# ir_transceiver.net
KiCad netlist of a schematic drawn in EAGLE
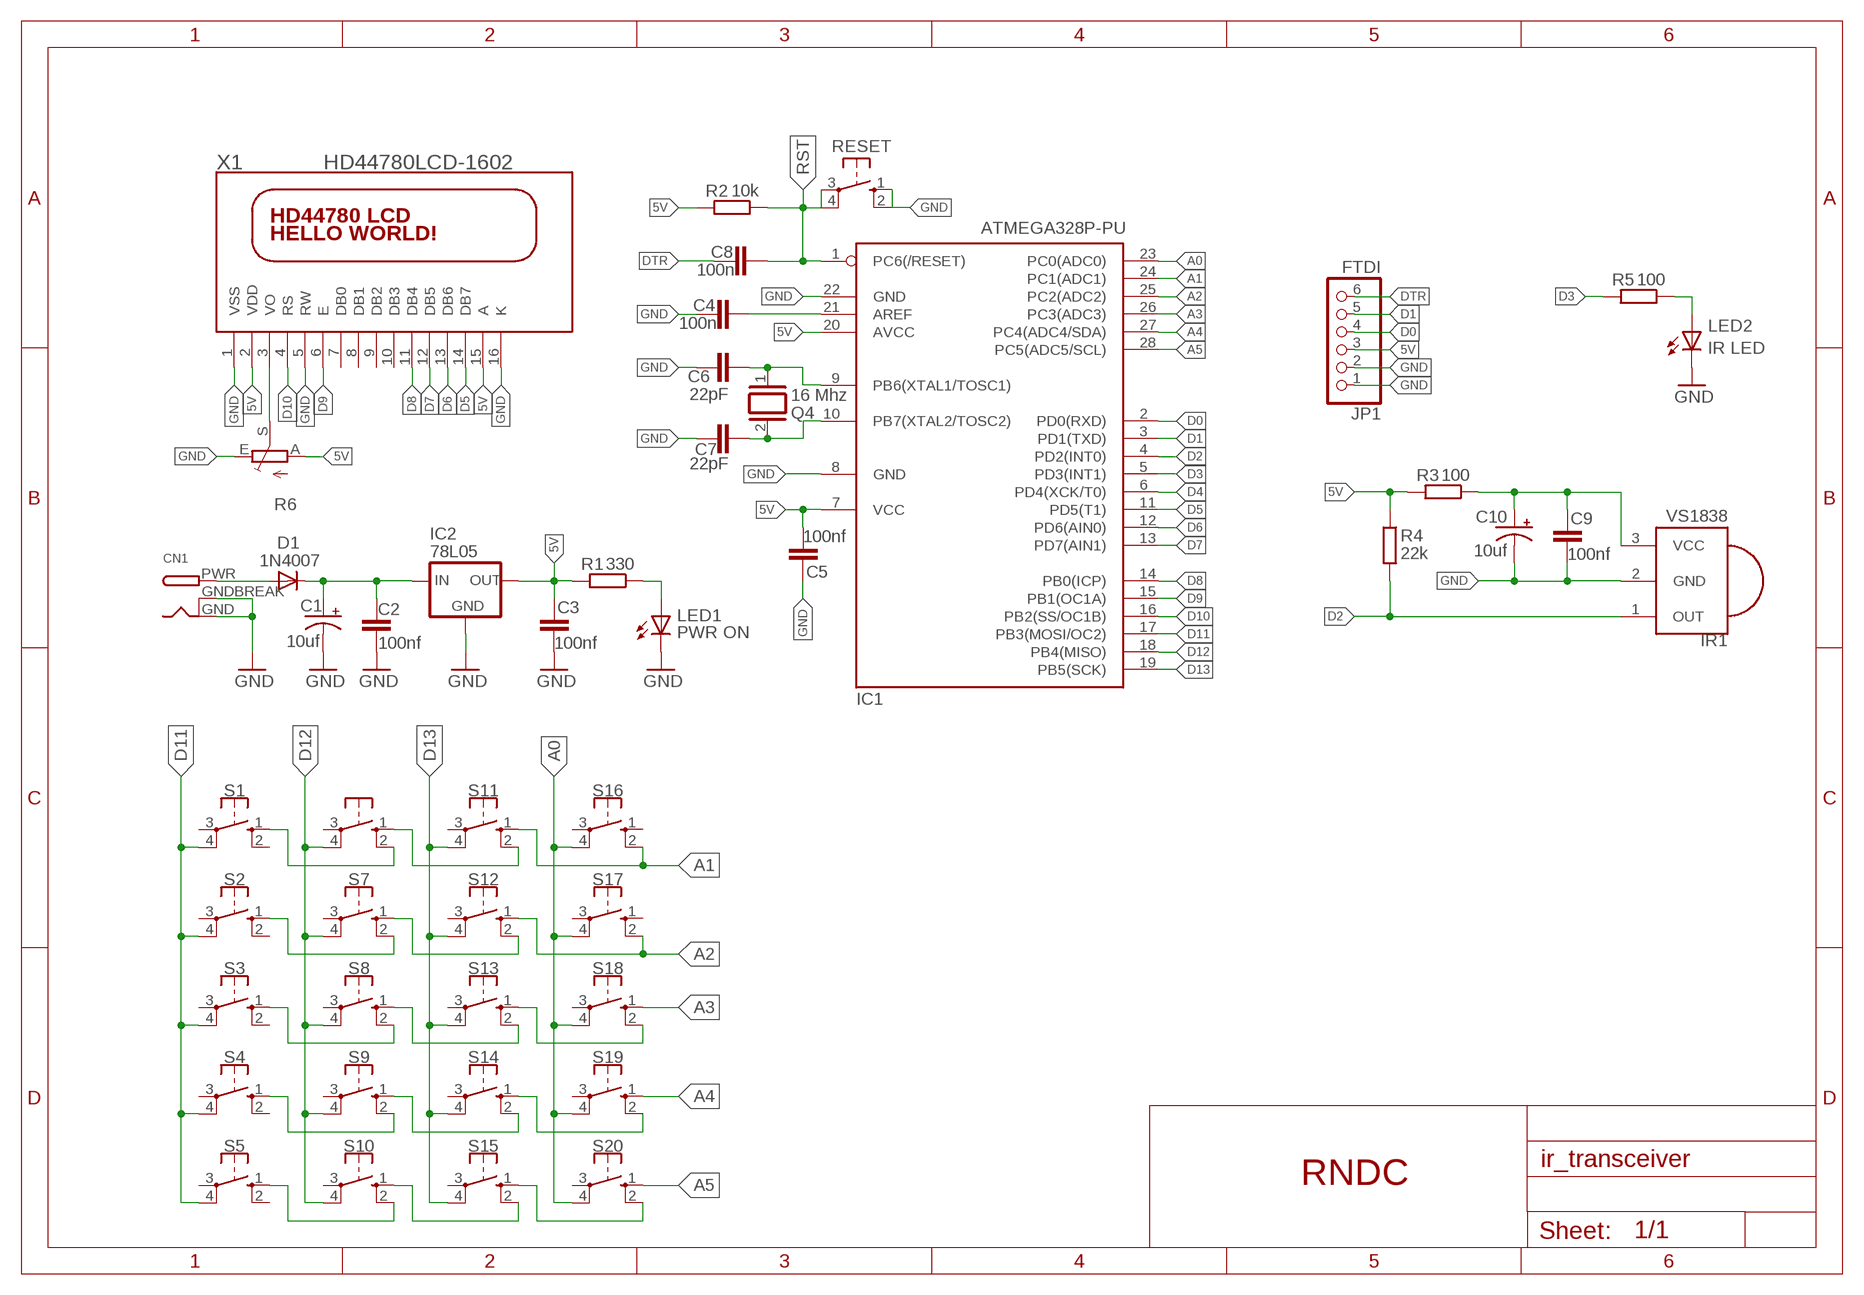
[diagram p0: schematic, sheet 1]

(export (version "E")
  (design (tool "Eeschema 10.0.6"))
  (components
    (comp (ref "C1")
      (value "10uf")
      (footprint "eagle-import:TT2D4")
      (libsource (lib "eagle-import") (part "CPOL-USTT2D4"))
    )
    (comp (ref "C2")
      (value "100nf")
      (footprint "eagle-import:C025-024X044")
      (libsource (lib "eagle-import") (part "C-EU025-024X044"))
    )
    (comp (ref "C3")
      (value "100nf")
      (footprint "eagle-import:C025-024X044")
      (libsource (lib "eagle-import") (part "C-EU025-024X044"))
    )
    (comp (ref "C4")
      (value "100n")
      (footprint "eagle-import:C025-024X044")
      (libsource (lib "eagle-import") (part "C-EU025-024X044"))
    )
    (comp (ref "C5")
      (value "100nf")
      (footprint "eagle-import:C025-024X044")
      (libsource (lib "eagle-import") (part "C-EU025-024X044"))
    )
    (comp (ref "C6")
      (value "22pF")
      (footprint "eagle-import:C025-024X044")
      (libsource (lib "eagle-import") (part "rcl_C-EU025-024X044"))
    )
    (comp (ref "C7")
      (value "22pF")
      (footprint "eagle-import:C025-024X044")
      (libsource (lib "eagle-import") (part "rcl_C-EU025-024X044"))
    )
    (comp (ref "C8")
      (value "100n")
      (footprint "eagle-import:C025-024X044")
      (libsource (lib "eagle-import") (part "C-EU025-024X044"))
    )
    (comp (ref "C9")
      (value "100nf")
      (footprint "eagle-import:C025-024X044")
      (libsource (lib "eagle-import") (part "C-EU025-024X044"))
    )
    (comp (ref "C10")
      (value "10uf")
      (footprint "eagle-import:TT2D4")
      (libsource (lib "eagle-import") (part "CPOL-USTT2D4"))
    )
    (comp (ref "CN1")
      (value "DCBARRELPTH")
      (footprint "eagle-import:DCJACK_2MM_PTH")
      (libsource (lib "eagle-import") (part "DCBARRELPTH"))
    )
    (comp (ref "D1")
      (value "1N4007")
      (footprint "eagle-import:DO35-7")
      (libsource (lib "eagle-import") (part "1N4148DO35-7"))
    )
    (comp (ref "IC1")
      (value "ATMEGA328P-PU")
      (footprint "eagle-import:DIL28-3")
      (libsource (lib "eagle-import") (part "ATMEGA328P-PU"))
    )
    (comp (ref "IC2")
      (value "78L05")
      (footprint "eagle-import:78LXX")
      (libsource (lib "eagle-import") (part "78LXX{dblquote}"))
    )
    (comp (ref "IR1")
      (value "VS1838")
      (footprint "eagle-import:VS1838")
      (libsource (lib "eagle-import") (part "VS1838"))
    )
    (comp (ref "JP1")
      (value "FTDI")
      (footprint "eagle-import:1X06")
      (libsource (lib "eagle-import") (part "PINHD-1X6"))
    )
    (comp (ref "LED1")
      (value "PWR ON")
      (footprint "eagle-import:LED3MM")
      (libsource (lib "eagle-import") (part "LED3MM"))
    )
    (comp (ref "LED2")
      (value "IR LED")
      (footprint "eagle-import:LED5MM")
      (libsource (lib "eagle-import") (part "LED5MM"))
    )
    (comp (ref "Q4")
      (value "16 Mhz")
      (footprint "eagle-import:QS")
      (libsource (lib "eagle-import") (part "XTAL/S"))
    )
    (comp (ref "R1")
      (value "330")
      (footprint "eagle-import:0207_10")
      (libsource (lib "eagle-import") (part "R-EU_0207_10"))
    )
    (comp (ref "R2")
      (value "10k")
      (footprint "eagle-import:0207_10")
      (libsource (lib "eagle-import") (part "R-EU_0207_10"))
    )
    (comp (ref "R3")
      (value "100")
      (footprint "eagle-import:0207_10")
      (libsource (lib "eagle-import") (part "R-EU_0207_10"))
    )
    (comp (ref "R4")
      (value "22k")
      (footprint "eagle-import:0207_10")
      (libsource (lib "eagle-import") (part "R-EU_0207_10"))
    )
    (comp (ref "R5")
      (value "100")
      (footprint "eagle-import:0207_10")
      (libsource (lib "eagle-import") (part "R-EU_0207_10"))
    )
    (comp (ref "R6")
      (value "TRIM_EU-CA6V")
      (footprint "eagle-import:CA6V")
      (libsource (lib "eagle-import") (part "TRIM_EU-CA6V"))
    )
    (comp (ref "RESET")
      (value "10-XX")
      (footprint "eagle-import:B3F-10XX")
      (fields (field (name "MPN") "B3F-1000"))
      (libsource (lib "eagle-import") (part "10-XX"))
    )
    (comp (ref "S1")
      (value "10-XX")
      (footprint "eagle-import:B3F-10XX")
      (fields (field (name "MPN") "B3F-1000"))
      (libsource (lib "eagle-import") (part "10-XX"))
    )
    (comp (ref "S2")
      (value "10-XX")
      (footprint "eagle-import:B3F-10XX")
      (fields (field (name "MPN") "B3F-1000"))
      (libsource (lib "eagle-import") (part "10-XX"))
    )
    (comp (ref "S3")
      (value "10-XX")
      (footprint "eagle-import:B3F-10XX")
      (fields (field (name "MPN") "B3F-1000"))
      (libsource (lib "eagle-import") (part "10-XX"))
    )
    (comp (ref "S4")
      (value "10-XX")
      (footprint "eagle-import:B3F-10XX")
      (fields (field (name "MPN") "B3F-1000"))
      (libsource (lib "eagle-import") (part "10-XX"))
    )
    (comp (ref "S5")
      (value "10-XX")
      (footprint "eagle-import:B3F-10XX")
      (fields (field (name "MPN") "B3F-1000"))
      (libsource (lib "eagle-import") (part "10-XX"))
    )
    (comp (ref "S6")
      (value "10-XX")
      (footprint "eagle-import:B3F-10XX")
      (fields (field (name "MPN") "B3F-1000"))
      (libsource (lib "eagle-import") (part "10-XX"))
    )
    (comp (ref "S7")
      (value "10-XX")
      (footprint "eagle-import:B3F-10XX")
      (fields (field (name "MPN") "B3F-1000"))
      (libsource (lib "eagle-import") (part "10-XX"))
    )
    (comp (ref "S8")
      (value "10-XX")
      (footprint "eagle-import:B3F-10XX")
      (fields (field (name "MPN") "B3F-1000"))
      (libsource (lib "eagle-import") (part "10-XX"))
    )
    (comp (ref "S9")
      (value "10-XX")
      (footprint "eagle-import:B3F-10XX")
      (fields (field (name "MPN") "B3F-1000"))
      (libsource (lib "eagle-import") (part "10-XX"))
    )
    (comp (ref "S10")
      (value "10-XX")
      (footprint "eagle-import:B3F-10XX")
      (fields (field (name "MPN") "B3F-1000"))
      (libsource (lib "eagle-import") (part "10-XX"))
    )
    (comp (ref "S11")
      (value "10-XX")
      (footprint "eagle-import:B3F-10XX")
      (fields (field (name "MPN") "B3F-1000"))
      (libsource (lib "eagle-import") (part "10-XX"))
    )
    (comp (ref "S12")
      (value "10-XX")
      (footprint "eagle-import:B3F-10XX")
      (fields (field (name "MPN") "B3F-1000"))
      (libsource (lib "eagle-import") (part "10-XX"))
    )
    (comp (ref "S13")
      (value "10-XX")
      (footprint "eagle-import:B3F-10XX")
      (fields (field (name "MPN") "B3F-1000"))
      (libsource (lib "eagle-import") (part "10-XX"))
    )
    (comp (ref "S14")
      (value "10-XX")
      (footprint "eagle-import:B3F-10XX")
      (fields (field (name "MPN") "B3F-1000"))
      (libsource (lib "eagle-import") (part "10-XX"))
    )
    (comp (ref "S15")
      (value "10-XX")
      (footprint "eagle-import:B3F-10XX")
      (fields (field (name "MPN") "B3F-1000"))
      (libsource (lib "eagle-import") (part "10-XX"))
    )
    (comp (ref "S16")
      (value "10-XX")
      (footprint "eagle-import:B3F-10XX")
      (fields (field (name "MPN") "B3F-1000"))
      (libsource (lib "eagle-import") (part "10-XX"))
    )
    (comp (ref "S17")
      (value "10-XX")
      (footprint "eagle-import:B3F-10XX")
      (fields (field (name "MPN") "B3F-1000"))
      (libsource (lib "eagle-import") (part "10-XX"))
    )
    (comp (ref "S18")
      (value "10-XX")
      (footprint "eagle-import:B3F-10XX")
      (fields (field (name "MPN") "B3F-1000"))
      (libsource (lib "eagle-import") (part "10-XX"))
    )
    (comp (ref "S19")
      (value "10-XX")
      (footprint "eagle-import:B3F-10XX")
      (fields (field (name "MPN") "B3F-1000"))
      (libsource (lib "eagle-import") (part "10-XX"))
    )
    (comp (ref "S20")
      (value "10-XX")
      (footprint "eagle-import:B3F-10XX")
      (fields (field (name "MPN") "B3F-1000"))
      (libsource (lib "eagle-import") (part "10-XX"))
    )
    (comp (ref "X1")
      (value "HD44780LCD-1602")
      (footprint "eagle-import:LCD1602")
      (libsource (lib "eagle-import") (part "HD44780LCD-1602"))
    )
  )
  (nets
    (net (code "1") (name "5V") (class "Default")
      (node (ref "C3") (pin "2") (pinfunction "2_2") (pintype "passive"))
      (node (ref "C5") (pin "2") (pinfunction "2_2") (pintype "passive"))
      (node (ref "IC1") (pin "20") (pinfunction "AVCC_20") (pintype "power_in"))
      (node (ref "IC1") (pin "7") (pinfunction "VCC_7") (pintype "power_in"))
      (node (ref "IC2") (pin "OUT") (pinfunction "OUT_OUT") (pintype "passive"))
      (node (ref "JP1") (pin "3") (pinfunction "3_3") (pintype "passive"))
      (node (ref "R1") (pin "2") (pinfunction "2_2") (pintype "passive"))
      (node (ref "R2") (pin "2") (pinfunction "2_2") (pintype "passive"))
      (node (ref "R3") (pin "2") (pinfunction "2_2") (pintype "passive"))
      (node (ref "R4") (pin "1") (pinfunction "1_1") (pintype "passive"))
      (node (ref "R6") (pin "A") (pinfunction "A_A") (pintype "passive"))
      (node (ref "X1") (pin "15") (pinfunction "A_15") (pintype "input"))
      (node (ref "X1") (pin "2") (pinfunction "VDD_2") (pintype "power_in"))
    )
    (net (code "2") (name "A0") (class "Default")
      (node (ref "IC1") (pin "23") (pinfunction "PC0(ADC0)_23") (pintype "bidirectional"))
      (node (ref "S16") (pin "4") (pinfunction "P1_4") (pintype "passive"))
      (node (ref "S17") (pin "4") (pinfunction "P1_4") (pintype "passive"))
      (node (ref "S18") (pin "4") (pinfunction "P1_4") (pintype "passive"))
      (node (ref "S19") (pin "4") (pinfunction "P1_4") (pintype "passive"))
      (node (ref "S20") (pin "4") (pinfunction "P1_4") (pintype "passive"))
    )
    (net (code "3") (name "A1") (class "Default")
      (node (ref "IC1") (pin "24") (pinfunction "PC1(ADC1)_24") (pintype "bidirectional"))
      (node (ref "S11") (pin "1") (pinfunction "S_1") (pintype "passive"))
      (node (ref "S16") (pin "2") (pinfunction "S1_2") (pintype "passive"))
    )
    (net (code "4") (name "A2") (class "Default")
      (node (ref "IC1") (pin "25") (pinfunction "PC2(ADC2)_25") (pintype "bidirectional"))
      (node (ref "S12") (pin "1") (pinfunction "S_1") (pintype "passive"))
      (node (ref "S17") (pin "2") (pinfunction "S1_2") (pintype "passive"))
    )
    (net (code "5") (name "A3") (class "Default")
      (node (ref "IC1") (pin "26") (pinfunction "PC3(ADC3)_26") (pintype "bidirectional"))
      (node (ref "S18") (pin "1") (pinfunction "S_1") (pintype "passive"))
    )
    (net (code "6") (name "A4") (class "Default")
      (node (ref "IC1") (pin "27") (pinfunction "PC4(ADC4/SDA)_27") (pintype "bidirectional"))
      (node (ref "S19") (pin "1") (pinfunction "S_1") (pintype "passive"))
    )
    (net (code "7") (name "A5") (class "Default")
      (node (ref "IC1") (pin "28") (pinfunction "PC5(ADC5/SCL)_28") (pintype "bidirectional"))
      (node (ref "S20") (pin "1") (pinfunction "S_1") (pintype "passive"))
    )
    (net (code "8") (name "D0") (class "Default")
      (node (ref "IC1") (pin "2") (pinfunction "PD0(RXD)_2") (pintype "bidirectional"))
      (node (ref "JP1") (pin "4") (pinfunction "4_4") (pintype "passive"))
    )
    (net (code "9") (name "D1") (class "Default")
      (node (ref "IC1") (pin "3") (pinfunction "PD1(TXD)_3") (pintype "bidirectional"))
      (node (ref "JP1") (pin "5") (pinfunction "5_5") (pintype "passive"))
    )
    (net (code "10") (name "D2") (class "Default")
      (node (ref "IC1") (pin "4") (pinfunction "PD2(INT0)_4") (pintype "bidirectional"))
      (node (ref "IR1") (pin "1") (pinfunction "OUT_1") (pintype "output"))
      (node (ref "R4") (pin "2") (pinfunction "2_2") (pintype "passive"))
    )
    (net (code "11") (name "D3") (class "Default")
      (node (ref "IC1") (pin "5") (pinfunction "PD3(INT1)_5") (pintype "bidirectional"))
      (node (ref "R5") (pin "2") (pinfunction "2_2") (pintype "passive"))
    )
    (net (code "12") (name "D4") (class "Default")
      (node (ref "IC1") (pin "6") (pinfunction "PD4(XCK/T0)_6") (pintype "bidirectional"))
    )
    (net (code "13") (name "D5") (class "Default")
      (node (ref "IC1") (pin "11") (pinfunction "PD5(T1)_11") (pintype "bidirectional"))
      (node (ref "X1") (pin "14") (pinfunction "DB7_14") (pintype "bidirectional"))
    )
    (net (code "14") (name "D6") (class "Default")
      (node (ref "IC1") (pin "12") (pinfunction "PD6(AIN0)_12") (pintype "bidirectional"))
      (node (ref "X1") (pin "13") (pinfunction "DB6_13") (pintype "bidirectional"))
    )
    (net (code "15") (name "D7") (class "Default")
      (node (ref "IC1") (pin "13") (pinfunction "PD7(AIN1)_13") (pintype "bidirectional"))
      (node (ref "X1") (pin "12") (pinfunction "DB5_12") (pintype "bidirectional"))
    )
    (net (code "16") (name "D8") (class "Default")
      (node (ref "IC1") (pin "14") (pinfunction "PB0(ICP)_14") (pintype "bidirectional"))
      (node (ref "X1") (pin "11") (pinfunction "DB4_11") (pintype "bidirectional"))
    )
    (net (code "17") (name "D9") (class "Default")
      (node (ref "IC1") (pin "15") (pinfunction "PB1(OC1A)_15") (pintype "bidirectional"))
      (node (ref "X1") (pin "6") (pinfunction "E_6") (pintype "input"))
    )
    (net (code "18") (name "D10") (class "Default")
      (node (ref "IC1") (pin "16") (pinfunction "PB2(SS/OC1B)_16") (pintype "bidirectional"))
      (node (ref "X1") (pin "4") (pinfunction "RS_4") (pintype "input"))
    )
    (net (code "19") (name "D11") (class "Default")
      (node (ref "IC1") (pin "17") (pinfunction "PB3(MOSI/OC2)_17") (pintype "bidirectional"))
      (node (ref "S1") (pin "4") (pinfunction "P1_4") (pintype "passive"))
      (node (ref "S2") (pin "4") (pinfunction "P1_4") (pintype "passive"))
      (node (ref "S3") (pin "4") (pinfunction "P1_4") (pintype "passive"))
      (node (ref "S4") (pin "4") (pinfunction "P1_4") (pintype "passive"))
      (node (ref "S5") (pin "4") (pinfunction "P1_4") (pintype "passive"))
    )
    (net (code "20") (name "D12") (class "Default")
      (node (ref "IC1") (pin "18") (pinfunction "PB4(MISO)_18") (pintype "bidirectional"))
      (node (ref "S10") (pin "4") (pinfunction "P1_4") (pintype "passive"))
      (node (ref "S6") (pin "4") (pinfunction "P1_4") (pintype "passive"))
      (node (ref "S7") (pin "4") (pinfunction "P1_4") (pintype "passive"))
      (node (ref "S8") (pin "4") (pinfunction "P1_4") (pintype "passive"))
      (node (ref "S9") (pin "4") (pinfunction "P1_4") (pintype "passive"))
    )
    (net (code "21") (name "D13") (class "Default")
      (node (ref "IC1") (pin "19") (pinfunction "PB5(SCK)_19") (pintype "bidirectional"))
      (node (ref "S11") (pin "4") (pinfunction "P1_4") (pintype "passive"))
      (node (ref "S12") (pin "4") (pinfunction "P1_4") (pintype "passive"))
      (node (ref "S13") (pin "4") (pinfunction "P1_4") (pintype "passive"))
      (node (ref "S14") (pin "4") (pinfunction "P1_4") (pintype "passive"))
      (node (ref "S15") (pin "4") (pinfunction "P1_4") (pintype "passive"))
    )
    (net (code "22") (name "DTR") (class "Default")
      (node (ref "C8") (pin "1") (pinfunction "1_1") (pintype "passive"))
      (node (ref "JP1") (pin "6") (pinfunction "6_6") (pintype "passive"))
    )
    (net (code "23") (name "GND") (class "Default")
      (node (ref "C1") (pin "-") (pinfunction "-_-") (pintype "passive"))
      (node (ref "C10") (pin "-") (pinfunction "-_-") (pintype "passive"))
      (node (ref "C2") (pin "1") (pinfunction "1_1") (pintype "passive"))
      (node (ref "C3") (pin "1") (pinfunction "1_1") (pintype "passive"))
      (node (ref "C4") (pin "1") (pinfunction "1_1") (pintype "passive"))
      (node (ref "C5") (pin "1") (pinfunction "1_1") (pintype "passive"))
      (node (ref "C6") (pin "2") (pinfunction "2_2") (pintype "passive"))
      (node (ref "C7") (pin "2") (pinfunction "2_2") (pintype "passive"))
      (node (ref "C9") (pin "1") (pinfunction "1_1") (pintype "passive"))
      (node (ref "CN1") (pin "GND") (pinfunction "GND_GND") (pintype "power_in"))
      (node (ref "CN1") (pin "GNDBREAK") (pinfunction "GNDBREAK_GNDBREAK") (pintype "power_in"))
      (node (ref "IC1") (pin "22") (pinfunction "GND_22") (pintype "power_in"))
      (node (ref "IC1") (pin "8") (pinfunction "GND_8") (pintype "power_in"))
      (node (ref "IC2") (pin "GND") (pinfunction "GND_GND") (pintype "input"))
      (node (ref "IR1") (pin "2") (pinfunction "GND_2") (pintype "power_in"))
      (node (ref "JP1") (pin "1") (pinfunction "1_1") (pintype "passive"))
      (node (ref "JP1") (pin "2") (pinfunction "2_2") (pintype "passive"))
      (node (ref "LED1") (pin "K") (pinfunction "C_K") (pintype "passive"))
      (node (ref "LED2") (pin "K") (pinfunction "C_K") (pintype "passive"))
      (node (ref "R6") (pin "E") (pinfunction "E_E") (pintype "passive"))
      (node (ref "RESET") (pin "1") (pinfunction "S_1") (pintype "passive"))
      (node (ref "RESET") (pin "2") (pinfunction "S1_2") (pintype "passive"))
      (node (ref "X1") (pin "1") (pinfunction "VSS_1") (pintype "power_in"))
      (node (ref "X1") (pin "16") (pinfunction "K_16") (pintype "input"))
      (node (ref "X1") (pin "5") (pinfunction "RW_5") (pintype "input"))
    )
    (net (code "24") (name "Net-(C1-Pad+)") (class "Default")
      (node (ref "C1") (pin "+") (pinfunction "+_+") (pintype "passive"))
      (node (ref "C2") (pin "2") (pinfunction "2_2") (pintype "passive"))
      (node (ref "D1") (pin "C") (pinfunction "C_C") (pintype "passive"))
      (node (ref "IC2") (pin "IN") (pinfunction "IN_IN") (pintype "input"))
    )
    (net (code "25") (name "Net-(CN1-PadPWR)") (class "Default")
      (node (ref "CN1") (pin "PWR") (pinfunction "PWR_PWR") (pintype "power_in"))
      (node (ref "D1") (pin "A") (pinfunction "A_A") (pintype "passive"))
    )
    (net (code "26") (name "Net-(IC1-AREF)") (class "Default")
      (node (ref "C4") (pin "2") (pinfunction "2_2") (pintype "passive"))
      (node (ref "IC1") (pin "21") (pinfunction "AREF_21") (pintype "passive"))
    )
    (net (code "27") (name "Net-(IC1-PB6(XTAL1{slash}TOSC1))") (class "Default")
      (node (ref "C6") (pin "1") (pinfunction "1_1") (pintype "passive"))
      (node (ref "IC1") (pin "9") (pinfunction "PB6(XTAL1/TOSC1)_9") (pintype "bidirectional"))
      (node (ref "Q4") (pin "1") (pinfunction "1_1") (pintype "passive"))
    )
    (net (code "28") (name "Net-(IC1-PB7(XTAL2{slash}TOSC2))") (class "Default")
      (node (ref "C7") (pin "1") (pinfunction "1_1") (pintype "passive"))
      (node (ref "IC1") (pin "10") (pinfunction "PB7(XTAL2/TOSC2)_10") (pintype "bidirectional"))
      (node (ref "Q4") (pin "2") (pinfunction "2_2") (pintype "passive"))
    )
    (net (code "29") (name "Net-(IR1-VCC)") (class "Default")
      (node (ref "C10") (pin "+") (pinfunction "+_+") (pintype "passive"))
      (node (ref "C9") (pin "2") (pinfunction "2_2") (pintype "passive"))
      (node (ref "IR1") (pin "3") (pinfunction "VCC_3") (pintype "power_in"))
      (node (ref "R3") (pin "1") (pinfunction "1_1") (pintype "passive"))
    )
    (net (code "30") (name "Net-(LED1-PadA)") (class "Default")
      (node (ref "LED1") (pin "A") (pinfunction "A_A") (pintype "passive"))
      (node (ref "R1") (pin "1") (pinfunction "1_1") (pintype "passive"))
    )
    (net (code "31") (name "Net-(LED2-PadA)") (class "Default")
      (node (ref "LED2") (pin "A") (pinfunction "A_A") (pintype "passive"))
      (node (ref "R5") (pin "1") (pinfunction "1_1") (pintype "passive"))
    )
    (net (code "32") (name "Net-(S1-S)") (class "Default")
      (node (ref "S1") (pin "1") (pinfunction "S_1") (pintype "passive"))
      (node (ref "S6") (pin "2") (pinfunction "S1_2") (pintype "passive"))
    )
    (net (code "33") (name "Net-(S2-S)") (class "Default")
      (node (ref "S2") (pin "1") (pinfunction "S_1") (pintype "passive"))
      (node (ref "S7") (pin "2") (pinfunction "S1_2") (pintype "passive"))
    )
    (net (code "34") (name "Net-(S3-S)") (class "Default")
      (node (ref "S3") (pin "1") (pinfunction "S_1") (pintype "passive"))
      (node (ref "S8") (pin "2") (pinfunction "S1_2") (pintype "passive"))
    )
    (net (code "35") (name "Net-(S4-S)") (class "Default")
      (node (ref "S4") (pin "1") (pinfunction "S_1") (pintype "passive"))
      (node (ref "S9") (pin "2") (pinfunction "S1_2") (pintype "passive"))
    )
    (net (code "36") (name "Net-(S10-S)") (class "Default")
      (node (ref "S10") (pin "1") (pinfunction "S_1") (pintype "passive"))
      (node (ref "S15") (pin "2") (pinfunction "S1_2") (pintype "passive"))
    )
    (net (code "37") (name "Net-(S10-S1)") (class "Default")
      (node (ref "S10") (pin "2") (pinfunction "S1_2") (pintype "passive"))
      (node (ref "S5") (pin "1") (pinfunction "S_1") (pintype "passive"))
    )
    (net (code "38") (name "Net-(S11-S1)") (class "Default")
      (node (ref "S11") (pin "2") (pinfunction "S1_2") (pintype "passive"))
      (node (ref "S6") (pin "1") (pinfunction "S_1") (pintype "passive"))
    )
    (net (code "39") (name "Net-(S12-S1)") (class "Default")
      (node (ref "S12") (pin "2") (pinfunction "S1_2") (pintype "passive"))
      (node (ref "S7") (pin "1") (pinfunction "S_1") (pintype "passive"))
    )
    (net (code "40") (name "Net-(S13-S)") (class "Default")
      (node (ref "S13") (pin "1") (pinfunction "S_1") (pintype "passive"))
      (node (ref "S18") (pin "2") (pinfunction "S1_2") (pintype "passive"))
    )
    (net (code "41") (name "Net-(S13-S1)") (class "Default")
      (node (ref "S13") (pin "2") (pinfunction "S1_2") (pintype "passive"))
      (node (ref "S8") (pin "1") (pinfunction "S_1") (pintype "passive"))
    )
    (net (code "42") (name "Net-(S14-S)") (class "Default")
      (node (ref "S14") (pin "1") (pinfunction "S_1") (pintype "passive"))
      (node (ref "S19") (pin "2") (pinfunction "S1_2") (pintype "passive"))
    )
    (net (code "43") (name "Net-(S14-S1)") (class "Default")
      (node (ref "S14") (pin "2") (pinfunction "S1_2") (pintype "passive"))
      (node (ref "S9") (pin "1") (pinfunction "S_1") (pintype "passive"))
    )
    (net (code "44") (name "Net-(S15-S)") (class "Default")
      (node (ref "S15") (pin "1") (pinfunction "S_1") (pintype "passive"))
      (node (ref "S20") (pin "2") (pinfunction "S1_2") (pintype "passive"))
    )
    (net (code "45") (name "Net-(X1-VO)") (class "Default")
      (node (ref "R6") (pin "S") (pinfunction "S_S") (pintype "passive"))
      (node (ref "X1") (pin "3") (pinfunction "VO_3") (pintype "input"))
    )
    (net (code "46") (name "RST") (class "Default")
      (node (ref "C8") (pin "2") (pinfunction "2_2") (pintype "passive"))
      (node (ref "IC1") (pin "1") (pinfunction "PC6(/RESET)_1") (pintype "bidirectional"))
      (node (ref "R2") (pin "1") (pinfunction "1_1") (pintype "passive"))
      (node (ref "RESET") (pin "3") (pinfunction "P_3") (pintype "passive"))
      (node (ref "RESET") (pin "4") (pinfunction "P1_4") (pintype "passive"))
    )
    (net (code "47") (name "unconnected-(S1-P-Pad3)") (class "Default")
      (node (ref "S1") (pin "3") (pinfunction "P_3") (pintype "passive"))
    )
    (net (code "48") (name "unconnected-(S1-S1-Pad2)") (class "Default")
      (node (ref "S1") (pin "2") (pinfunction "S1_2") (pintype "passive"))
    )
    (net (code "49") (name "unconnected-(S2-P-Pad3)") (class "Default")
      (node (ref "S2") (pin "3") (pinfunction "P_3") (pintype "passive"))
    )
    (net (code "50") (name "unconnected-(S2-S1-Pad2)") (class "Default")
      (node (ref "S2") (pin "2") (pinfunction "S1_2") (pintype "passive"))
    )
    (net (code "51") (name "unconnected-(S3-P-Pad3)") (class "Default")
      (node (ref "S3") (pin "3") (pinfunction "P_3") (pintype "passive"))
    )
    (net (code "52") (name "unconnected-(S3-S1-Pad2)") (class "Default")
      (node (ref "S3") (pin "2") (pinfunction "S1_2") (pintype "passive"))
    )
    (net (code "53") (name "unconnected-(S4-P-Pad3)") (class "Default")
      (node (ref "S4") (pin "3") (pinfunction "P_3") (pintype "passive"))
    )
    (net (code "54") (name "unconnected-(S4-S1-Pad2)") (class "Default")
      (node (ref "S4") (pin "2") (pinfunction "S1_2") (pintype "passive"))
    )
    (net (code "55") (name "unconnected-(S5-P-Pad3)") (class "Default")
      (node (ref "S5") (pin "3") (pinfunction "P_3") (pintype "passive"))
    )
    (net (code "56") (name "unconnected-(S5-S1-Pad2)") (class "Default")
      (node (ref "S5") (pin "2") (pinfunction "S1_2") (pintype "passive"))
    )
    (net (code "57") (name "unconnected-(S6-P-Pad3)") (class "Default")
      (node (ref "S6") (pin "3") (pinfunction "P_3") (pintype "passive"))
    )
    (net (code "58") (name "unconnected-(S7-P-Pad3)") (class "Default")
      (node (ref "S7") (pin "3") (pinfunction "P_3") (pintype "passive"))
    )
    (net (code "59") (name "unconnected-(S8-P-Pad3)") (class "Default")
      (node (ref "S8") (pin "3") (pinfunction "P_3") (pintype "passive"))
    )
    (net (code "60") (name "unconnected-(S9-P-Pad3)") (class "Default")
      (node (ref "S9") (pin "3") (pinfunction "P_3") (pintype "passive"))
    )
    (net (code "61") (name "unconnected-(S10-P-Pad3)") (class "Default")
      (node (ref "S10") (pin "3") (pinfunction "P_3") (pintype "passive"))
    )
    (net (code "62") (name "unconnected-(S11-P-Pad3)") (class "Default")
      (node (ref "S11") (pin "3") (pinfunction "P_3") (pintype "passive"))
    )
    (net (code "63") (name "unconnected-(S12-P-Pad3)") (class "Default")
      (node (ref "S12") (pin "3") (pinfunction "P_3") (pintype "passive"))
    )
    (net (code "64") (name "unconnected-(S13-P-Pad3)") (class "Default")
      (node (ref "S13") (pin "3") (pinfunction "P_3") (pintype "passive"))
    )
    (net (code "65") (name "unconnected-(S14-P-Pad3)") (class "Default")
      (node (ref "S14") (pin "3") (pinfunction "P_3") (pintype "passive"))
    )
    (net (code "66") (name "unconnected-(S15-P-Pad3)") (class "Default")
      (node (ref "S15") (pin "3") (pinfunction "P_3") (pintype "passive"))
    )
    (net (code "67") (name "unconnected-(S16-P-Pad3)") (class "Default")
      (node (ref "S16") (pin "3") (pinfunction "P_3") (pintype "passive"))
    )
    (net (code "68") (name "unconnected-(S16-S-Pad1)") (class "Default")
      (node (ref "S16") (pin "1") (pinfunction "S_1") (pintype "passive"))
    )
    (net (code "69") (name "unconnected-(S17-P-Pad3)") (class "Default")
      (node (ref "S17") (pin "3") (pinfunction "P_3") (pintype "passive"))
    )
    (net (code "70") (name "unconnected-(S17-S-Pad1)") (class "Default")
      (node (ref "S17") (pin "1") (pinfunction "S_1") (pintype "passive"))
    )
    (net (code "71") (name "unconnected-(S18-P-Pad3)") (class "Default")
      (node (ref "S18") (pin "3") (pinfunction "P_3") (pintype "passive"))
    )
    (net (code "72") (name "unconnected-(S19-P-Pad3)") (class "Default")
      (node (ref "S19") (pin "3") (pinfunction "P_3") (pintype "passive"))
    )
    (net (code "73") (name "unconnected-(S20-P-Pad3)") (class "Default")
      (node (ref "S20") (pin "3") (pinfunction "P_3") (pintype "passive"))
    )
    (net (code "74") (name "unconnected-(X1-DB0-Pad7)") (class "Default")
      (node (ref "X1") (pin "7") (pinfunction "DB0_7") (pintype "bidirectional"))
    )
    (net (code "75") (name "unconnected-(X1-DB1-Pad8)") (class "Default")
      (node (ref "X1") (pin "8") (pinfunction "DB1_8") (pintype "bidirectional"))
    )
    (net (code "76") (name "unconnected-(X1-DB2-Pad9)") (class "Default")
      (node (ref "X1") (pin "9") (pinfunction "DB2_9") (pintype "bidirectional"))
    )
    (net (code "77") (name "unconnected-(X1-DB3-Pad10)") (class "Default")
      (node (ref "X1") (pin "10") (pinfunction "DB3_10") (pintype "bidirectional"))
    )
  )
)
